# HammerHacks_II_Badge_PCB.net
KiCad netlist of a schematic drawn in EasyEDA Pro
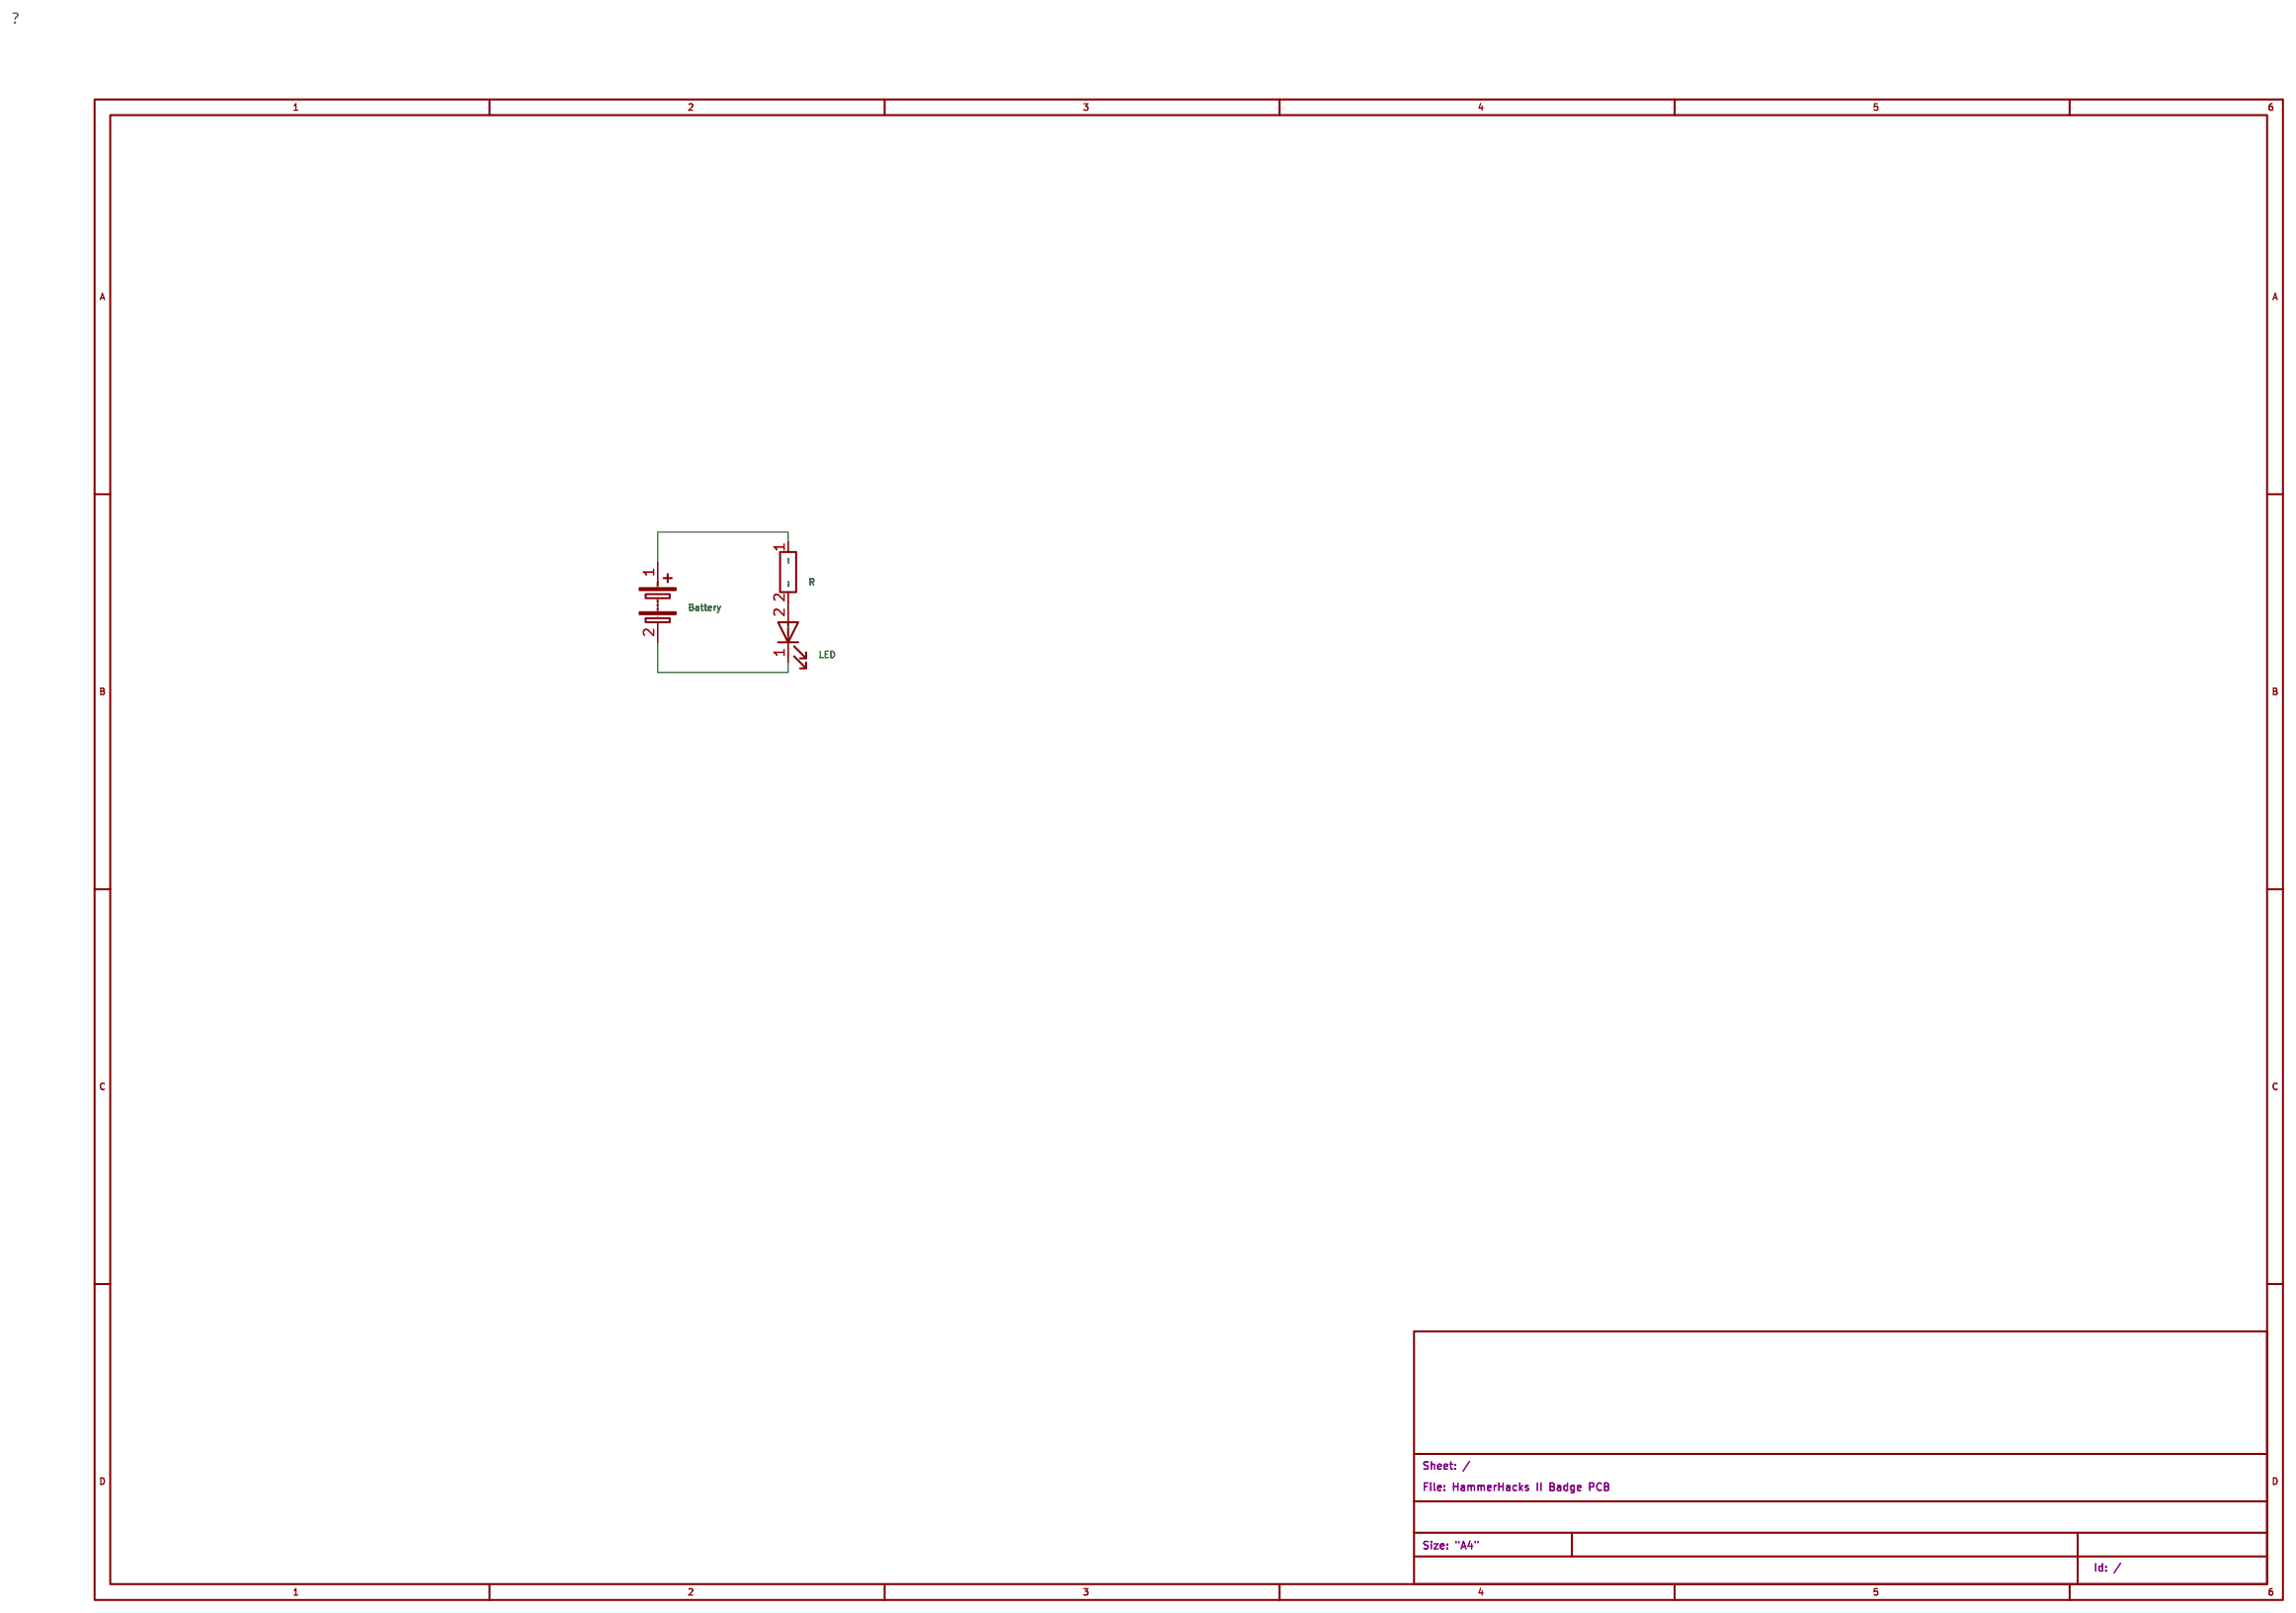
[diagram p0: schematic sheet]

(export (version "E")
  (design (tool "Eeschema 10.0.6"))
  (components
    (comp (ref "BT1")
      (value "Battery")
      (footprint "easyedapro:Battery:BatteryHolder_Keystone_3034_1x20mm")
      (description "Multiple-cell battery")
      (libsource (lib "easyedapro") (part "Device_Battery"))
    )
    (comp (ref "D1")
      (value "LED")
      (footprint "easyedapro:LED_THT:LED_D3.0mm")
      (description "Light emitting diode")
      (libsource (lib "easyedapro") (part "Device_LED"))
    )
    (comp (ref "R1")
      (value "R")
      (footprint "easyedapro:RES-TH_BD2.3-L6.3-P10.3-D0.6")
      (description "Resistor")
      (libsource (lib "easyedapro") (part "Device_R"))
    )
  )
  (nets
    (net (code "1") (name "Net-(BT1-+)") (class "Default")
      (node (ref "BT1") (pin "1") (pinfunction "+_1") (pintype "unspecified"))
      (node (ref "R1") (pin "1") (pinfunction "~_1") (pintype "unspecified"))
    )
    (net (code "2") (name "Net-(BT1--)") (class "Default")
      (node (ref "BT1") (pin "2") (pinfunction "-_2") (pintype "unspecified"))
      (node (ref "D1") (pin "1") (pinfunction "K_1") (pintype "unspecified"))
    )
    (net (code "3") (name "Net-(D1-A)") (class "Default")
      (node (ref "D1") (pin "2") (pinfunction "A_2") (pintype "unspecified"))
      (node (ref "R1") (pin "2") (pinfunction "~_2") (pintype "unspecified"))
    )
  )
)
